# oven_high_voltage.net
KiCad netlist of a schematic drawn in EAGLE
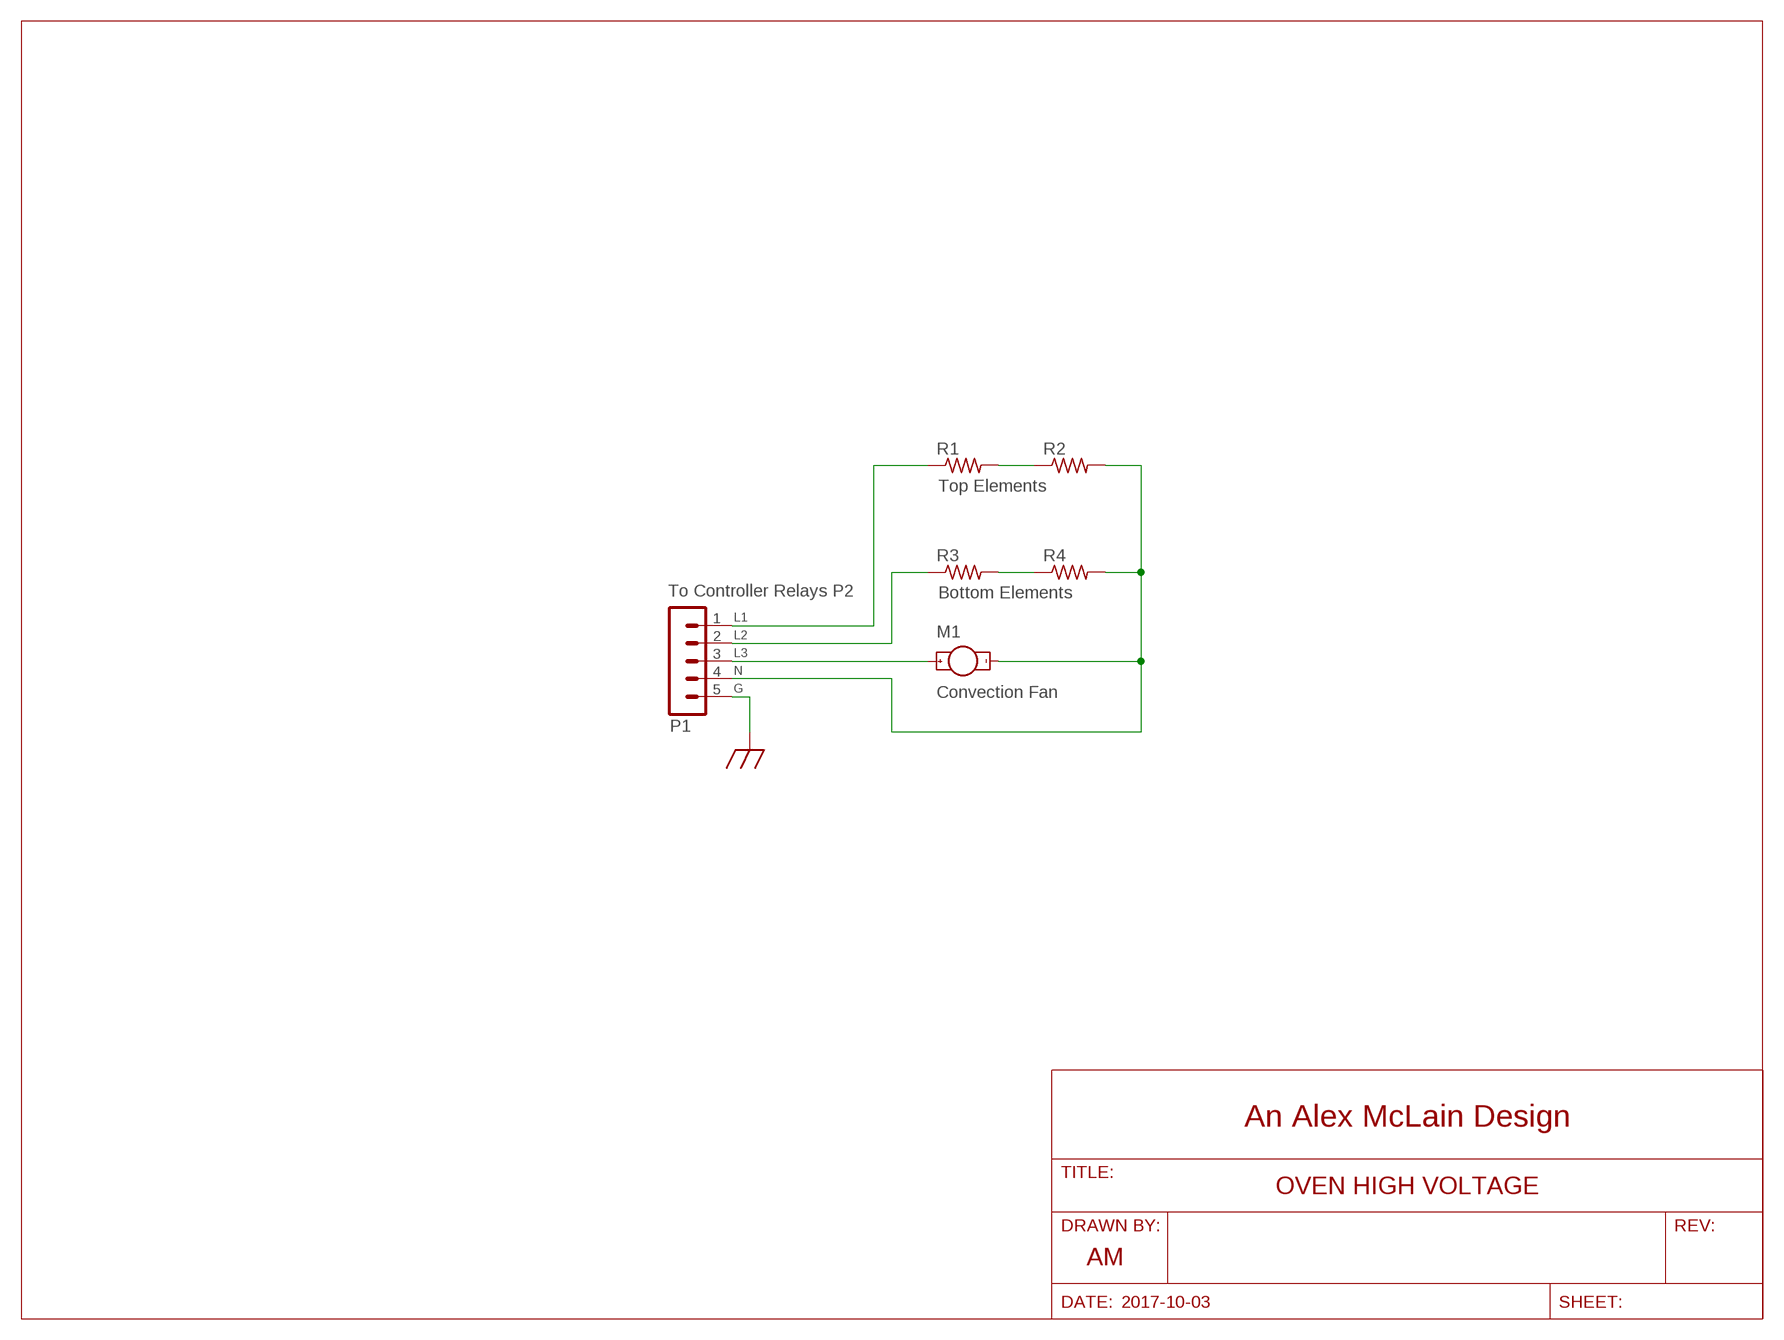
[diagram p0: schematic, sheet 1]

(export (version "E")
  (design (tool "Eeschema 10.0.6"))
  (components
    (comp (ref "M1")
      (value "Convection Fan")
      (footprint "eagle-import:VIBE-MOTOR-10MM")
      (libsource (lib "eagle-import") (part "MOTOR10MM"))
    )
    (comp (ref "P1")
      (value "MA05-1")
      (footprint "eagle-import:MA05-1")
      (libsource (lib "eagle-import") (part "MA05-1"))
    )
    (comp (ref "R1")
      (value "R-US_0204/7")
      (footprint "eagle-import:0204_7")
      (libsource (lib "eagle-import") (part "R-US_0204/7"))
    )
    (comp (ref "R2")
      (value "R-US_0204/7")
      (footprint "eagle-import:0204_7")
      (libsource (lib "eagle-import") (part "R-US_0204/7"))
    )
    (comp (ref "R3")
      (value "R-US_0204/7")
      (footprint "eagle-import:0204_7")
      (libsource (lib "eagle-import") (part "R-US_0204/7"))
    )
    (comp (ref "R4")
      (value "R-US_0204/7")
      (footprint "eagle-import:0204_7")
      (libsource (lib "eagle-import") (part "R-US_0204/7"))
    )
  )
  (nets
    (net (code "1") (name "CGND") (class "Default")
      (node (ref "P1") (pin "5") (pinfunction "5_5") (pintype "passive"))
    )
    (net (code "2") (name "Net-(M1-Pad+)") (class "Default")
      (node (ref "M1") (pin "+") (pinfunction "+_+") (pintype "bidirectional"))
      (node (ref "P1") (pin "3") (pinfunction "3_3") (pintype "passive"))
    )
    (net (code "3") (name "Net-(M1-Pad-)") (class "Default")
      (node (ref "M1") (pin "-") (pinfunction "-_-") (pintype "bidirectional"))
      (node (ref "P1") (pin "4") (pinfunction "4_4") (pintype "passive"))
      (node (ref "R2") (pin "2") (pinfunction "2_2") (pintype "passive"))
      (node (ref "R4") (pin "2") (pinfunction "2_2") (pintype "passive"))
    )
    (net (code "4") (name "Net-(P1-Pad1)") (class "Default")
      (node (ref "P1") (pin "1") (pinfunction "1_1") (pintype "passive"))
      (node (ref "R1") (pin "1") (pinfunction "1_1") (pintype "passive"))
    )
    (net (code "5") (name "Net-(P1-Pad2)") (class "Default")
      (node (ref "P1") (pin "2") (pinfunction "2_2") (pintype "passive"))
      (node (ref "R3") (pin "1") (pinfunction "1_1") (pintype "passive"))
    )
    (net (code "6") (name "Net-(R1-Pad2)") (class "Default")
      (node (ref "R1") (pin "2") (pinfunction "2_2") (pintype "passive"))
      (node (ref "R2") (pin "1") (pinfunction "1_1") (pintype "passive"))
    )
    (net (code "7") (name "Net-(R3-Pad2)") (class "Default")
      (node (ref "R3") (pin "2") (pinfunction "2_2") (pintype "passive"))
      (node (ref "R4") (pin "1") (pinfunction "1_1") (pintype "passive"))
    )
  )
)
